# design.net
KiCad netlist of a schematic drawn in Altium Designer
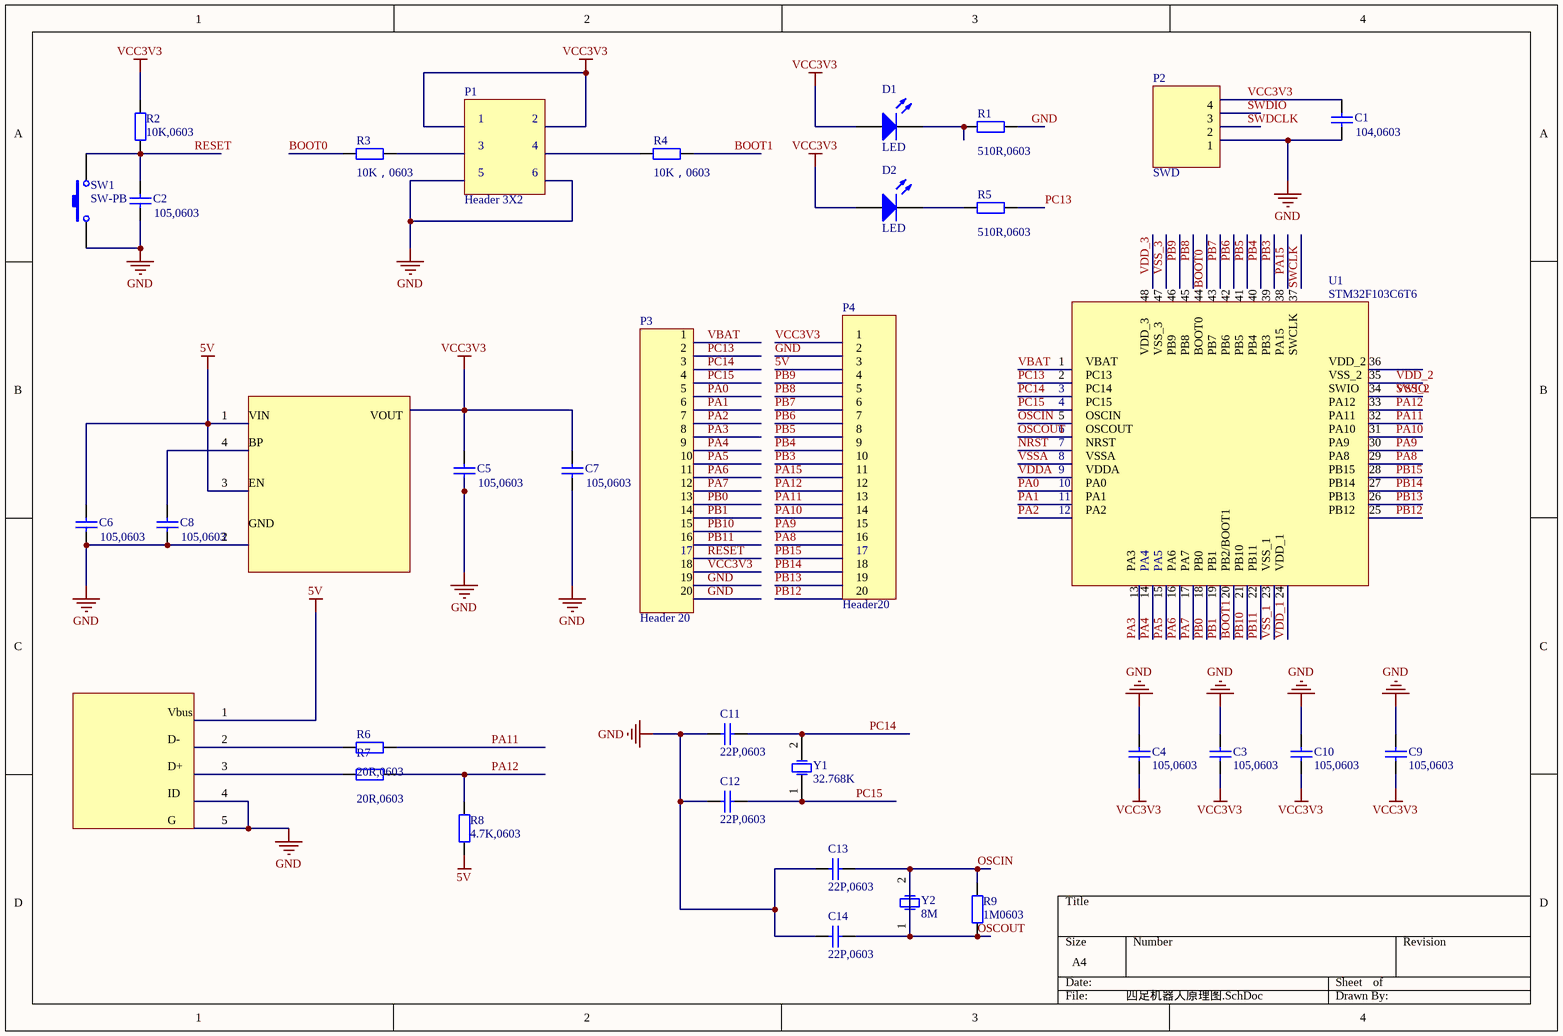
[diagram p0: 四足机器人原理图.SchDoc]

(export (version "E")
  (design (tool "Eeschema 10.0.6"))
  (components
    (comp (ref "C1")
      (value "104,0603")
      (footprint "RAD-0.3")
      (description "Capacitor")
      (fields (field (name "Comment") "Cap") (field (name "PUBLISHER") "Altium Limited"))
      (libsource (lib "Miscellaneous Devices") (part "Cap"))
    )
    (comp (ref "C2")
      (value "105,0603")
      (footprint "RAD-0.3")
      (description "Capacitor")
      (fields (field (name "Comment") "Cap") (field (name "PUBLISHER") "Altium Limited"))
      (libsource (lib "Miscellaneous Devices") (part "Cap"))
    )
    (comp (ref "C3")
      (value "105,0603")
      (footprint "RAD-0.3")
      (description "Capacitor")
      (fields (field (name "Comment") "Cap") (field (name "PUBLISHER") "Altium Limited"))
      (libsource (lib "Miscellaneous Devices") (part "Cap"))
    )
    (comp (ref "C4")
      (value "105,0603")
      (footprint "RAD-0.3")
      (description "Capacitor")
      (fields (field (name "Comment") "Cap") (field (name "PUBLISHER") "Altium Limited"))
      (libsource (lib "Miscellaneous Devices") (part "Cap"))
    )
    (comp (ref "C5")
      (value "105,0603")
      (footprint "RAD-0.3")
      (description "Capacitor")
      (fields (field (name "Comment") "Cap") (field (name "PUBLISHER") "Altium Limited"))
      (libsource (lib "Miscellaneous Devices") (part "Cap"))
    )
    (comp (ref "C6")
      (value "105,0603")
      (footprint "RAD-0.3")
      (description "Capacitor")
      (fields (field (name "Comment") "Cap") (field (name "PUBLISHER") "Altium Limited"))
      (libsource (lib "Miscellaneous Devices") (part "Cap"))
    )
    (comp (ref "C7")
      (value "105,0603")
      (footprint "RAD-0.3")
      (description "Capacitor")
      (fields (field (name "Comment") "Cap") (field (name "PUBLISHER") "Altium Limited"))
      (libsource (lib "Miscellaneous Devices") (part "Cap"))
    )
    (comp (ref "C8")
      (value "105,0603")
      (footprint "RAD-0.3")
      (description "Capacitor")
      (fields (field (name "Comment") "Cap") (field (name "PUBLISHER") "Altium Limited"))
      (libsource (lib "Miscellaneous Devices") (part "Cap"))
    )
    (comp (ref "C9")
      (value "105,0603")
      (footprint "RAD-0.3")
      (description "Capacitor")
      (fields (field (name "Comment") "Cap") (field (name "PUBLISHER") "Altium Limited"))
      (libsource (lib "Miscellaneous Devices") (part "Cap"))
    )
    (comp (ref "C10")
      (value "105,0603")
      (footprint "RAD-0.3")
      (description "Capacitor")
      (fields (field (name "Comment") "Cap") (field (name "PUBLISHER") "Altium Limited"))
      (libsource (lib "Miscellaneous Devices") (part "Cap"))
    )
    (comp (ref "C11")
      (value "22P,0603")
      (footprint "RAD-0.3")
      (description "Capacitor")
      (fields (field (name "Comment") "Cap") (field (name "PUBLISHER") "Altium Limited"))
      (libsource (lib "Miscellaneous Devices") (part "Cap"))
    )
    (comp (ref "C12")
      (value "22P,0603")
      (footprint "RAD-0.3")
      (description "Capacitor")
      (fields (field (name "Comment") "Cap") (field (name "PUBLISHER") "Altium Limited"))
      (libsource (lib "Miscellaneous Devices") (part "Cap"))
    )
    (comp (ref "C13")
      (value "22P,0603")
      (footprint "RAD-0.3")
      (description "Capacitor")
      (fields (field (name "Comment") "Cap") (field (name "PUBLISHER") "Altium Limited"))
      (libsource (lib "Miscellaneous Devices") (part "Cap"))
    )
    (comp (ref "C14")
      (value "22P,0603")
      (footprint "RAD-0.3")
      (description "Capacitor")
      (fields (field (name "Comment") "Cap") (field (name "PUBLISHER") "Altium Limited"))
      (libsource (lib "Miscellaneous Devices") (part "Cap"))
    )
    (comp (ref "D1")
      (value "LED")
      (footprint "LED-0")
      (description "Typical INFRARED GaAs LED")
      (fields (field (name "PUBLISHER") "Altium Limited"))
      (libsource (lib "Miscellaneous Devices") (part "LED0"))
    )
    (comp (ref "D2")
      (value "LED")
      (footprint "LED-0")
      (description "Typical INFRARED GaAs LED")
      (fields (field (name "PUBLISHER") "Altium Limited"))
      (libsource (lib "Miscellaneous Devices") (part "LED0"))
    )
    (comp (ref "R1")
      (value "510R,0603")
      (footprint "AXIAL-0.4")
      (description "Resistor")
      (fields (field (name "Comment") "Res2") (field (name "PUBLISHER") "Altium Limited"))
      (libsource (lib "Miscellaneous Devices") (part "Res2"))
    )
    (comp (ref "R2")
      (value "10K,0603")
      (footprint "AXIAL-0.4")
      (description "Resistor")
      (fields (field (name "Comment") "Res2") (field (name "PUBLISHER") "Altium Limited"))
      (libsource (lib "") (part "Res2_1"))
    )
    (comp (ref "R3")
      (value "10K，0603")
      (footprint "AXIAL-0.4")
      (description "Resistor")
      (fields (field (name "Comment") "Res2") (field (name "PUBLISHER") "Altium Limited"))
      (libsource (lib "Miscellaneous Devices") (part "Res2"))
    )
    (comp (ref "R4")
      (value "10K，0603")
      (footprint "AXIAL-0.4")
      (description "Resistor")
      (fields (field (name "Comment") "Res2") (field (name "PUBLISHER") "Altium Limited"))
      (libsource (lib "Miscellaneous Devices") (part "Res2"))
    )
    (comp (ref "R5")
      (value "510R,0603")
      (footprint "AXIAL-0.4")
      (description "Resistor")
      (fields (field (name "Comment") "Res2") (field (name "PUBLISHER") "Altium Limited"))
      (libsource (lib "Miscellaneous Devices") (part "Res2"))
    )
    (comp (ref "R6")
      (value "20R,0603")
      (footprint "AXIAL-0.4")
      (description "Resistor")
      (fields (field (name "Comment") "Res2") (field (name "PUBLISHER") "Altium Limited"))
      (libsource (lib "Miscellaneous Devices") (part "Res2"))
    )
    (comp (ref "R7")
      (value "20R,0603")
      (footprint "AXIAL-0.4")
      (description "Resistor")
      (fields (field (name "Comment") "Res2") (field (name "PUBLISHER") "Altium Limited"))
      (libsource (lib "Miscellaneous Devices") (part "Res2"))
    )
    (comp (ref "R8")
      (value "4.7K,0603")
      (footprint "AXIAL-0.4")
      (description "Resistor")
      (fields (field (name "Comment") "Res2") (field (name "PUBLISHER") "Altium Limited"))
      (libsource (lib "") (part "Res2_1"))
    )
    (comp (ref "R9")
      (value "1M0603")
      (footprint "AXIAL-0.4")
      (description "Resistor")
      (fields (field (name "Comment") "Res2") (field (name "PUBLISHER") "Altium Limited"))
      (libsource (lib "") (part "Res2_1"))
    )
    (comp (ref "SW1")
      (value "SW-PB")
      (footprint "SPST-2")
      (description "Switch")
      (fields (field (name "PUBLISHER") "Altium Limited"))
      (libsource (lib "Miscellaneous Devices") (part "SW-PB"))
    )
    (comp (ref "Y1")
      (value "32.768K")
      (footprint "R38")
      (description "Crystal Oscillator")
      (fields (field (name "PUBLISHER") "Altium Limited"))
      (libsource (lib "Miscellaneous Devices") (part "XTAL"))
    )
    (comp (ref "Y2")
      (value "8M")
      (footprint "R38")
      (description "Crystal Oscillator")
      (fields (field (name "PUBLISHER") "Altium Limited"))
      (libsource (lib "Miscellaneous Devices") (part "XTAL"))
    )
  )
  (nets
    (net (code "1") (name "/OSCIN") (class "Default")
      (node (ref "C13") (pin "1") (pinfunction "1_1") (pintype "passive"))
      (node (ref "C14") (pin "1") (pinfunction "1_1") (pintype "passive"))
      (node (ref "R9") (pin "1") (pinfunction "1_1") (pintype "passive"))
      (node (ref "R9") (pin "2") (pinfunction "2_2") (pintype "passive"))
      (node (ref "Y2") (pin "1") (pinfunction "OSC1_1") (pintype "passive"))
      (node (ref "Y2") (pin "2") (pinfunction "OSC2_2") (pintype "passive"))
    )
    (net (code "10") (name "/PA11") (class "Default")
      (node (ref "R6") (pin "2") (pinfunction "2_2") (pintype "passive"))
    )
    (net (code "11") (name "/PA12") (class "Default")
      (node (ref "R7") (pin "2") (pinfunction "2_2") (pintype "passive"))
      (node (ref "R8") (pin "2") (pinfunction "2_2") (pintype "passive"))
    )
    (net (code "17") (name "/PC14") (class "Default")
      (node (ref "C11") (pin "1") (pinfunction "1_1") (pintype "passive"))
      (node (ref "Y1") (pin "2") (pinfunction "OSC2_2") (pintype "passive"))
    )
    (net (code "18") (name "/PC15") (class "Default")
      (node (ref "C12") (pin "1") (pinfunction "1_1") (pintype "passive"))
      (node (ref "Y1") (pin "1") (pinfunction "OSC1_1") (pintype "passive"))
    )
    (net (code "21") (name "5V") (class "Default")
      (node (ref "C6") (pin "2") (pinfunction "2_2") (pintype "passive"))
      (node (ref "R8") (pin "1") (pinfunction "1_1") (pintype "passive"))
    )
    (net (code "22") (name "GND") (class "Default")
      (node (ref "C1") (pin "1") (pinfunction "1_1") (pintype "passive"))
      (node (ref "C10") (pin "1") (pinfunction "1_1") (pintype "passive"))
      (node (ref "C11") (pin "2") (pinfunction "2_2") (pintype "passive"))
      (node (ref "C12") (pin "2") (pinfunction "2_2") (pintype "passive"))
      (node (ref "C13") (pin "2") (pinfunction "2_2") (pintype "passive"))
      (node (ref "C14") (pin "2") (pinfunction "2_2") (pintype "passive"))
      (node (ref "C2") (pin "1") (pinfunction "1_1") (pintype "passive"))
      (node (ref "C3") (pin "1") (pinfunction "1_1") (pintype "passive"))
      (node (ref "C4") (pin "1") (pinfunction "1_1") (pintype "passive"))
      (node (ref "C5") (pin "1") (pinfunction "1_1") (pintype "passive"))
      (node (ref "C6") (pin "1") (pinfunction "1_1") (pintype "passive"))
      (node (ref "C7") (pin "1") (pinfunction "1_1") (pintype "passive"))
      (node (ref "C8") (pin "1") (pinfunction "1_1") (pintype "passive"))
      (node (ref "C9") (pin "1") (pinfunction "1_1") (pintype "passive"))
      (node (ref "SW1") (pin "1") (pinfunction "1_1") (pintype "passive"))
    )
    (net (code "23") (name "Net-(C2-Pad2)") (class "Default")
      (node (ref "C2") (pin "2") (pinfunction "2_2") (pintype "passive"))
      (node (ref "R2") (pin "1") (pinfunction "1_1") (pintype "passive"))
      (node (ref "SW1") (pin "2") (pinfunction "2_2") (pintype "passive"))
    )
    (net (code "24") (name "Net-(D1-K)") (class "Default")
      (node (ref "D1") (pin "2") (pinfunction "K_2") (pintype "passive"))
      (node (ref "R1") (pin "1") (pinfunction "1_1") (pintype "passive"))
    )
    (net (code "25") (name "Net-(D2-K)") (class "Default")
      (node (ref "D2") (pin "2") (pinfunction "K_2") (pintype "passive"))
      (node (ref "R5") (pin "1") (pinfunction "1_1") (pintype "passive"))
    )
    (net (code "26") (name "VCC3V3") (class "Default")
      (node (ref "C10") (pin "2") (pinfunction "2_2") (pintype "passive"))
      (node (ref "C3") (pin "2") (pinfunction "2_2") (pintype "passive"))
      (node (ref "C4") (pin "2") (pinfunction "2_2") (pintype "passive"))
      (node (ref "C5") (pin "2") (pinfunction "2_2") (pintype "passive"))
      (node (ref "C7") (pin "2") (pinfunction "2_2") (pintype "passive"))
      (node (ref "C9") (pin "2") (pinfunction "2_2") (pintype "passive"))
      (node (ref "D1") (pin "1") (pinfunction "A_1") (pintype "passive"))
      (node (ref "D2") (pin "1") (pinfunction "A_1") (pintype "passive"))
      (node (ref "R2") (pin "2") (pinfunction "2_2") (pintype "passive"))
    )
    (net (code "27") (name "unconnected-(C1-Pad2)") (class "Default")
      (node (ref "C1") (pin "2") (pinfunction "2_2") (pintype "passive"))
    )
    (net (code "28") (name "unconnected-(C8-Pad2)") (class "Default")
      (node (ref "C8") (pin "2") (pinfunction "2_2") (pintype "passive"))
    )
    (net (code "29") (name "unconnected-(R1-Pad2)") (class "Default")
      (node (ref "R1") (pin "2") (pinfunction "2_2") (pintype "passive"))
    )
    (net (code "30") (name "unconnected-(R3-Pad1)") (class "Default")
      (node (ref "R3") (pin "1") (pinfunction "1_1") (pintype "passive"))
    )
    (net (code "31") (name "unconnected-(R3-Pad2)") (class "Default")
      (node (ref "R3") (pin "2") (pinfunction "2_2") (pintype "passive"))
    )
    (net (code "32") (name "unconnected-(R4-Pad1)") (class "Default")
      (node (ref "R4") (pin "1") (pinfunction "1_1") (pintype "passive"))
    )
    (net (code "33") (name "unconnected-(R4-Pad2)") (class "Default")
      (node (ref "R4") (pin "2") (pinfunction "2_2") (pintype "passive"))
    )
    (net (code "34") (name "unconnected-(R5-Pad2)") (class "Default")
      (node (ref "R5") (pin "2") (pinfunction "2_2") (pintype "passive"))
    )
    (net (code "35") (name "unconnected-(R6-Pad1)") (class "Default")
      (node (ref "R6") (pin "1") (pinfunction "1_1") (pintype "passive"))
    )
    (net (code "36") (name "unconnected-(R7-Pad1)") (class "Default")
      (node (ref "R7") (pin "1") (pinfunction "1_1") (pintype "passive"))
    )
  )
)
